# LCD.net
KiCad netlist of a schematic drawn in Altium Designer
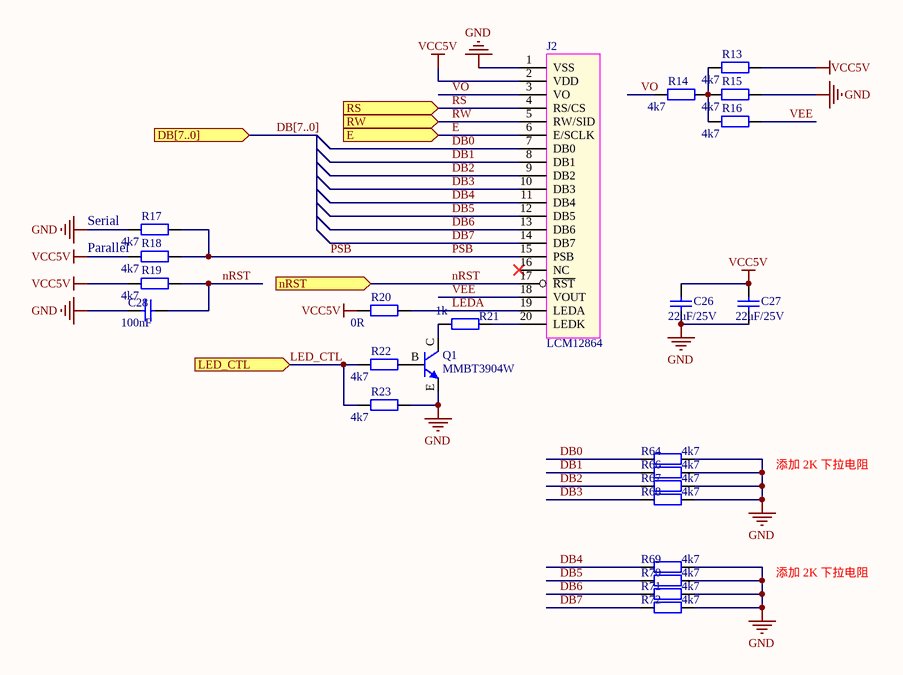
[diagram p0: LCD.SchDoc]

(export (version "E")
  (design (tool "Eeschema 10.0.6"))
  (components
    (comp (ref "C26") (value "22uF/25V") (footprint "C0805") (libsource (lib "myPCB") (part "CAP_08")))
    (comp (ref "C27") (value "22uF/25V") (footprint "C0805") (libsource (lib "myPCB") (part "CAP_08")))
    (comp (ref "C28") (value "100nF") (footprint "R0603") (libsource (lib "MyYX") (part "CAP_04")))
    (comp (ref "J2")
      (value "LCM12864")
      (footprint "LCD12864")
      (description "ST7920/LCM12864")
      (libsource (lib "MyYX") (part "LCM12864"))
    )
    (comp (ref "Q1") (value "MMBT3904W") (footprint "SOT_23") (libsource (lib "MyYX") (part "MMBT3904TT1G")))
    (comp (ref "R13") (value "4k7") (footprint "R0603") (libsource (lib "MyYX") (part "RES_04")))
    (comp (ref "R14") (value "4k7") (footprint "R0603") (libsource (lib "MyYX") (part "RES_04")))
    (comp (ref "R15") (value "4k7") (footprint "R0603") (libsource (lib "MyYX") (part "RES_04")))
    (comp (ref "R16") (value "4k7") (footprint "R0603") (libsource (lib "MyYX") (part "RES_04")))
    (comp (ref "R17") (value "4k7") (footprint "R0603") (libsource (lib "MyYX") (part "RES_04")))
    (comp (ref "R18") (value "4k7") (footprint "R0603") (libsource (lib "MyYX") (part "RES_04")))
    (comp (ref "R19") (value "4k7") (footprint "R0603") (libsource (lib "MyYX") (part "RES_04")))
    (comp (ref "R20") (value "0R") (footprint "R0603") (libsource (lib "MyYX") (part "RES_04")))
    (comp (ref "R21") (value "1k") (footprint "R0603") (libsource (lib "MyYX") (part "RES_04")))
    (comp (ref "R22") (value "4k7") (footprint "R0603") (libsource (lib "MyYX") (part "RES_04")))
    (comp (ref "R23") (value "4k7") (footprint "R0603") (libsource (lib "MyYX") (part "RES_04")))
    (comp (ref "R64") (value "4k7") (footprint "R0603") (libsource (lib "MyYX") (part "RES_04")))
    (comp (ref "R66") (value "4k7") (footprint "R0603") (libsource (lib "MyYX") (part "RES_04")))
    (comp (ref "R67") (value "4k7") (footprint "R0603") (libsource (lib "MyYX") (part "RES_04")))
    (comp (ref "R68") (value "4k7") (footprint "R0603") (libsource (lib "MyYX") (part "RES_04")))
    (comp (ref "R69") (value "4k7") (footprint "R0603") (libsource (lib "MyYX") (part "RES_04")))
    (comp (ref "R70") (value "4k7") (footprint "R0603") (libsource (lib "MyYX") (part "RES_04")))
    (comp (ref "R71") (value "4k7") (footprint "R0603") (libsource (lib "MyYX") (part "RES_04")))
    (comp (ref "R72") (value "4k7") (footprint "R0603") (libsource (lib "MyYX") (part "RES_04")))
  )
  (nets
    (net (code "1") (name "/DB0") (class "Default")
      (node (ref "J2") (pin "7") (pinfunction "DB0_7") (pintype "passive"))
      (node (ref "R64") (pin "1") (pinfunction "1_1") (pintype "passive"))
    )
    (net (code "2") (name "/DB1") (class "Default")
      (node (ref "J2") (pin "8") (pinfunction "DB1_8") (pintype "passive"))
      (node (ref "R66") (pin "1") (pinfunction "1_1") (pintype "passive"))
    )
    (net (code "3") (name "/DB2") (class "Default")
      (node (ref "J2") (pin "9") (pinfunction "DB2_9") (pintype "passive"))
      (node (ref "R67") (pin "1") (pinfunction "1_1") (pintype "passive"))
    )
    (net (code "4") (name "/DB3") (class "Default")
      (node (ref "J2") (pin "10") (pinfunction "DB3_10") (pintype "passive"))
      (node (ref "R68") (pin "1") (pinfunction "1_1") (pintype "passive"))
    )
    (net (code "5") (name "/DB4") (class "Default")
      (node (ref "J2") (pin "11") (pinfunction "DB4_11") (pintype "passive"))
      (node (ref "R69") (pin "1") (pinfunction "1_1") (pintype "passive"))
    )
    (net (code "6") (name "/DB5") (class "Default")
      (node (ref "J2") (pin "12") (pinfunction "DB5_12") (pintype "passive"))
      (node (ref "R70") (pin "1") (pinfunction "1_1") (pintype "passive"))
    )
    (net (code "7") (name "/DB6") (class "Default")
      (node (ref "J2") (pin "13") (pinfunction "DB6_13") (pintype "passive"))
      (node (ref "R71") (pin "1") (pinfunction "1_1") (pintype "passive"))
    )
    (net (code "8") (name "/DB7") (class "Default")
      (node (ref "J2") (pin "14") (pinfunction "DB7_14") (pintype "passive"))
      (node (ref "R72") (pin "1") (pinfunction "1_1") (pintype "passive"))
    )
    (net (code "10") (name "/E") (class "Default")
      (node (ref "J2") (pin "6") (pinfunction "E/SCLK_6") (pintype "passive"))
    )
    (net (code "11") (name "/LEDA") (class "Default")
      (node (ref "J2") (pin "19") (pinfunction "LEDA_19") (pintype "passive"))
      (node (ref "R20") (pin "2") (pinfunction "2_2") (pintype "passive"))
    )
    (net (code "12") (name "/LED_CTL") (class "Default")
      (node (ref "R22") (pin "1") (pinfunction "1_1") (pintype "passive"))
      (node (ref "R23") (pin "1") (pinfunction "1_1") (pintype "passive"))
    )
    (net (code "13") (name "/PSB") (class "Default")
      (node (ref "J2") (pin "15") (pinfunction "PSB_15") (pintype "passive"))
      (node (ref "R17") (pin "2") (pinfunction "2_2") (pintype "passive"))
      (node (ref "R18") (pin "2") (pinfunction "2_2") (pintype "passive"))
    )
    (net (code "14") (name "/RS") (class "Default")
      (node (ref "J2") (pin "4") (pinfunction "RS/CS_4") (pintype "passive"))
    )
    (net (code "15") (name "/RW") (class "Default")
      (node (ref "J2") (pin "5") (pinfunction "RW/SID_5") (pintype "passive"))
    )
    (net (code "16") (name "/VEE") (class "Default")
      (node (ref "J2") (pin "18") (pinfunction "VOUT_18") (pintype "passive"))
      (node (ref "R16") (pin "2") (pinfunction "2_2") (pintype "passive"))
    )
    (net (code "17") (name "/VO") (class "Default")
      (node (ref "J2") (pin "3") (pinfunction "VO_3") (pintype "passive"))
      (node (ref "R14") (pin "1") (pinfunction "1_1") (pintype "passive"))
    )
    (net (code "18") (name "/nRST") (class "Default")
      (node (ref "C28") (pin "2") (pinfunction "2_2") (pintype "passive"))
      (node (ref "J2") (pin "17") (pinfunction "~{RST}_17") (pintype "passive"))
      (node (ref "R19") (pin "2") (pinfunction "2_2") (pintype "passive"))
    )
    (net (code "19") (name "GND") (class "Default")
      (node (ref "C26") (pin "1") (pinfunction "1_1") (pintype "passive"))
      (node (ref "C27") (pin "1") (pinfunction "1_1") (pintype "passive"))
      (node (ref "C28") (pin "1") (pinfunction "1_1") (pintype "passive"))
      (node (ref "J2") (pin "1") (pinfunction "VSS_1") (pintype "passive"))
      (node (ref "Q1") (pin "E") (pinfunction "E_E") (pintype "passive"))
      (node (ref "R15") (pin "2") (pinfunction "2_2") (pintype "passive"))
      (node (ref "R17") (pin "1") (pinfunction "1_1") (pintype "passive"))
      (node (ref "R23") (pin "2") (pinfunction "2_2") (pintype "passive"))
      (node (ref "R64") (pin "2") (pinfunction "2_2") (pintype "passive"))
      (node (ref "R66") (pin "2") (pinfunction "2_2") (pintype "passive"))
      (node (ref "R67") (pin "2") (pinfunction "2_2") (pintype "passive"))
      (node (ref "R68") (pin "2") (pinfunction "2_2") (pintype "passive"))
      (node (ref "R69") (pin "2") (pinfunction "2_2") (pintype "passive"))
      (node (ref "R70") (pin "2") (pinfunction "2_2") (pintype "passive"))
      (node (ref "R71") (pin "2") (pinfunction "2_2") (pintype "passive"))
      (node (ref "R72") (pin "2") (pinfunction "2_2") (pintype "passive"))
    )
    (net (code "20") (name "Net-(J2-LEDK)") (class "Default")
      (node (ref "J2") (pin "20") (pinfunction "LEDK_20") (pintype "passive"))
      (node (ref "R21") (pin "2") (pinfunction "2_2") (pintype "passive"))
    )
    (net (code "21") (name "Net-(Q1-PadB)") (class "Default")
      (node (ref "Q1") (pin "B") (pinfunction "B_B") (pintype "passive"))
      (node (ref "R22") (pin "2") (pinfunction "2_2") (pintype "passive"))
    )
    (net (code "22") (name "Net-(Q1-PadC)") (class "Default")
      (node (ref "Q1") (pin "C") (pinfunction "C_C") (pintype "passive"))
      (node (ref "R21") (pin "1") (pinfunction "1_1") (pintype "passive"))
    )
    (net (code "23") (name "Net-(R13-Pad1)") (class "Default")
      (node (ref "R13") (pin "1") (pinfunction "1_1") (pintype "passive"))
      (node (ref "R14") (pin "2") (pinfunction "2_2") (pintype "passive"))
      (node (ref "R15") (pin "1") (pinfunction "1_1") (pintype "passive"))
      (node (ref "R16") (pin "1") (pinfunction "1_1") (pintype "passive"))
    )
    (net (code "24") (name "VCC5V") (class "Default")
      (node (ref "C26") (pin "2") (pinfunction "2_2") (pintype "passive"))
      (node (ref "C27") (pin "2") (pinfunction "2_2") (pintype "passive"))
      (node (ref "J2") (pin "2") (pinfunction "VDD_2") (pintype "passive"))
      (node (ref "R13") (pin "2") (pinfunction "2_2") (pintype "passive"))
      (node (ref "R18") (pin "1") (pinfunction "1_1") (pintype "passive"))
      (node (ref "R19") (pin "1") (pinfunction "1_1") (pintype "passive"))
      (node (ref "R20") (pin "1") (pinfunction "1_1") (pintype "passive"))
    )
    (net (code "25") (name "unconnected-(J2-NC-Pad16)") (class "Default")
      (node (ref "J2") (pin "16") (pinfunction "NC_16") (pintype "passive+no_connect"))
    )
  )
)
